# FPGA-Power.net
KiCad netlist of a schematic drawn in Altium Designer
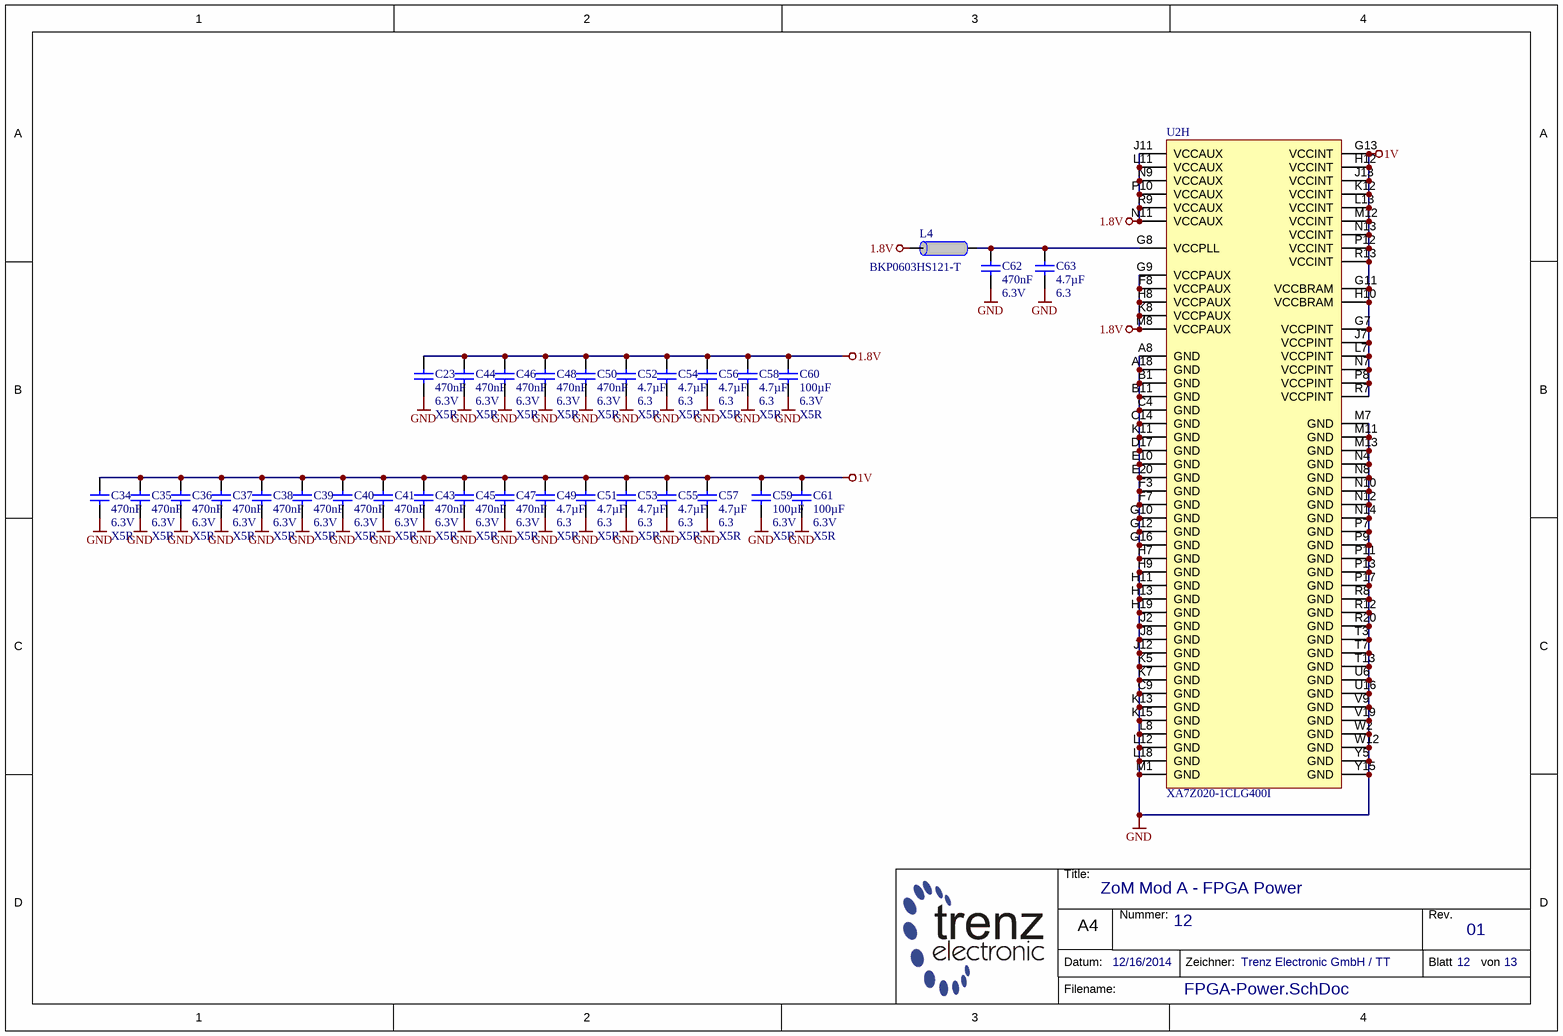
[diagram p0: FPGA-Power.SchDoc]

(export (version "E")
  (design (tool "Eeschema 10.0.6"))
  (components
    (comp (ref "C23")
      (value "470nF")
      (footprint "CAPC0603X33N")
      (description "KON 470nF X5R 6.3V SMD")
      (fields
        (field (name "VOLTAGE") "6.3V")
        (field (name "TECHNOLOGY") "X5R")
        (field (name "TOLERANCE") "20%")
      )
      (libsource (lib "TE") (part "CAP-NP"))
    )
    (comp (ref "C34")
      (value "470nF")
      (footprint "CAPC0603X33N")
      (description "KON 470nF X5R 6.3V SMD")
      (fields
        (field (name "VOLTAGE") "6.3V")
        (field (name "TECHNOLOGY") "X5R")
        (field (name "TOLERANCE") "20%")
      )
      (libsource (lib "TE") (part "CAP-NP"))
    )
    (comp (ref "C35")
      (value "470nF")
      (footprint "CAPC0603X33N")
      (description "KON 470nF X5R 6.3V SMD")
      (fields
        (field (name "VOLTAGE") "6.3V")
        (field (name "TECHNOLOGY") "X5R")
        (field (name "TOLERANCE") "20%")
      )
      (libsource (lib "TE") (part "CAP-NP"))
    )
    (comp (ref "C36")
      (value "470nF")
      (footprint "CAPC0603X33N")
      (description "KON 470nF X5R 6.3V SMD")
      (fields
        (field (name "VOLTAGE") "6.3V")
        (field (name "TECHNOLOGY") "X5R")
        (field (name "TOLERANCE") "20%")
      )
      (libsource (lib "TE") (part "CAP-NP"))
    )
    (comp (ref "C37")
      (value "470nF")
      (footprint "CAPC0603X33N")
      (description "KON 470nF X5R 6.3V SMD")
      (fields
        (field (name "VOLTAGE") "6.3V")
        (field (name "TECHNOLOGY") "X5R")
        (field (name "TOLERANCE") "20%")
      )
      (libsource (lib "TE") (part "CAP-NP"))
    )
    (comp (ref "C38")
      (value "470nF")
      (footprint "CAPC0603X33N")
      (description "KON 470nF X5R 6.3V SMD")
      (fields
        (field (name "VOLTAGE") "6.3V")
        (field (name "TECHNOLOGY") "X5R")
        (field (name "TOLERANCE") "20%")
      )
      (libsource (lib "TE") (part "CAP-NP"))
    )
    (comp (ref "C39")
      (value "470nF")
      (footprint "CAPC0603X33N")
      (description "KON 470nF X5R 6.3V SMD")
      (fields
        (field (name "VOLTAGE") "6.3V")
        (field (name "TECHNOLOGY") "X5R")
        (field (name "TOLERANCE") "20%")
      )
      (libsource (lib "TE") (part "CAP-NP"))
    )
    (comp (ref "C40")
      (value "470nF")
      (footprint "CAPC0603X33N")
      (description "KON 470nF X5R 6.3V SMD")
      (fields
        (field (name "VOLTAGE") "6.3V")
        (field (name "TECHNOLOGY") "X5R")
        (field (name "TOLERANCE") "20%")
      )
      (libsource (lib "TE") (part "CAP-NP"))
    )
    (comp (ref "C41")
      (value "470nF")
      (footprint "CAPC0603X33N")
      (description "KON 470nF X5R 6.3V SMD")
      (fields
        (field (name "VOLTAGE") "6.3V")
        (field (name "TECHNOLOGY") "X5R")
        (field (name "TOLERANCE") "20%")
      )
      (libsource (lib "TE") (part "CAP-NP"))
    )
    (comp (ref "C43")
      (value "470nF")
      (footprint "CAPC0603X33N")
      (description "KON 470nF X5R 6.3V SMD")
      (fields
        (field (name "VOLTAGE") "6.3V")
        (field (name "TECHNOLOGY") "X5R")
        (field (name "TOLERANCE") "20%")
      )
      (libsource (lib "TE") (part "CAP-NP"))
    )
    (comp (ref "C44")
      (value "470nF")
      (footprint "CAPC0603X33N")
      (description "KON 470nF X5R 6.3V SMD")
      (fields
        (field (name "VOLTAGE") "6.3V")
        (field (name "TECHNOLOGY") "X5R")
        (field (name "TOLERANCE") "20%")
      )
      (libsource (lib "TE") (part "CAP-NP"))
    )
    (comp (ref "C45")
      (value "470nF")
      (footprint "CAPC0603X33N")
      (description "KON 470nF X5R 6.3V SMD")
      (fields
        (field (name "VOLTAGE") "6.3V")
        (field (name "TECHNOLOGY") "X5R")
        (field (name "TOLERANCE") "20%")
      )
      (libsource (lib "TE") (part "CAP-NP"))
    )
    (comp (ref "C46")
      (value "470nF")
      (footprint "CAPC0603X33N")
      (description "KON 470nF X5R 6.3V SMD")
      (fields
        (field (name "VOLTAGE") "6.3V")
        (field (name "TECHNOLOGY") "X5R")
        (field (name "TOLERANCE") "20%")
      )
      (libsource (lib "TE") (part "CAP-NP"))
    )
    (comp (ref "C47")
      (value "470nF")
      (footprint "CAPC0603X33N")
      (description "KON 470nF X5R 6.3V SMD")
      (fields
        (field (name "VOLTAGE") "6.3V")
        (field (name "TECHNOLOGY") "X5R")
        (field (name "TOLERANCE") "20%")
      )
      (libsource (lib "TE") (part "CAP-NP"))
    )
    (comp (ref "C48")
      (value "470nF")
      (footprint "CAPC0603X33N")
      (description "KON 470nF X5R 6.3V SMD")
      (fields
        (field (name "VOLTAGE") "6.3V")
        (field (name "TECHNOLOGY") "X5R")
        (field (name "TOLERANCE") "20%")
      )
      (libsource (lib "TE") (part "CAP-NP"))
    )
    (comp (ref "C49")
      (value "4.7µF")
      (footprint "CAPC1005X60N")
      (description "KON 4.7µF 6.3V X5R SMD")
      (fields (field (name "VOLTAGE") "6.3") (field (name "TECHNOLOGY") "X5R"))
      (libsource (lib "TE") (part "CAP-NP"))
    )
    (comp (ref "C50")
      (value "470nF")
      (footprint "CAPC0603X33N")
      (description "KON 470nF X5R 6.3V SMD")
      (fields
        (field (name "VOLTAGE") "6.3V")
        (field (name "TECHNOLOGY") "X5R")
        (field (name "TOLERANCE") "20%")
      )
      (libsource (lib "TE") (part "CAP-NP"))
    )
    (comp (ref "C51")
      (value "4.7µF")
      (footprint "CAPC1005X60N")
      (description "KON 4.7µF 6.3V X5R SMD")
      (fields (field (name "VOLTAGE") "6.3") (field (name "TECHNOLOGY") "X5R"))
      (libsource (lib "TE") (part "CAP-NP"))
    )
    (comp (ref "C52")
      (value "4.7µF")
      (footprint "CAPC1005X60N")
      (description "KON 4.7µF 6.3V X5R SMD")
      (fields (field (name "VOLTAGE") "6.3") (field (name "TECHNOLOGY") "X5R"))
      (libsource (lib "TE") (part "CAP-NP"))
    )
    (comp (ref "C53")
      (value "4.7µF")
      (footprint "CAPC1005X60N")
      (description "KON 4.7µF 6.3V X5R SMD")
      (fields (field (name "VOLTAGE") "6.3") (field (name "TECHNOLOGY") "X5R"))
      (libsource (lib "TE") (part "CAP-NP"))
    )
    (comp (ref "C54")
      (value "4.7µF")
      (footprint "CAPC1005X60N")
      (description "KON 4.7µF 6.3V X5R SMD")
      (fields (field (name "VOLTAGE") "6.3") (field (name "TECHNOLOGY") "X5R"))
      (libsource (lib "TE") (part "CAP-NP"))
    )
    (comp (ref "C55")
      (value "4.7µF")
      (footprint "CAPC1005X60N")
      (description "KON 4.7µF 6.3V X5R SMD")
      (fields (field (name "VOLTAGE") "6.3") (field (name "TECHNOLOGY") "X5R"))
      (libsource (lib "TE") (part "CAP-NP"))
    )
    (comp (ref "C56")
      (value "4.7µF")
      (footprint "CAPC1005X60N")
      (description "KON 4.7µF 6.3V X5R SMD")
      (fields (field (name "VOLTAGE") "6.3") (field (name "TECHNOLOGY") "X5R"))
      (libsource (lib "TE") (part "CAP-NP"))
    )
    (comp (ref "C57")
      (value "4.7µF")
      (footprint "CAPC1005X60N")
      (description "KON 4.7µF 6.3V X5R SMD")
      (fields (field (name "VOLTAGE") "6.3") (field (name "TECHNOLOGY") "X5R"))
      (libsource (lib "TE") (part "CAP-NP"))
    )
    (comp (ref "C58")
      (value "4.7µF")
      (footprint "CAPC1005X60N")
      (description "KON 4.7µF 6.3V X5R SMD")
      (fields (field (name "VOLTAGE") "6.3") (field (name "TECHNOLOGY") "X5R"))
      (libsource (lib "TE") (part "CAP-NP"))
    )
    (comp (ref "C59")
      (value "100µF")
      (footprint "CAPC3216X180N")
      (description "KON 100µF 6,3V X5R SMD")
      (fields (field (name "VOLTAGE") "6.3V") (field (name "TECHNOLOGY") "X5R"))
      (libsource (lib "TE") (part "CAP-NP"))
    )
    (comp (ref "C60")
      (value "100µF")
      (footprint "CAPC3216X180N")
      (description "KON 100µF 6,3V X5R SMD")
      (fields (field (name "VOLTAGE") "6.3V") (field (name "TECHNOLOGY") "X5R"))
      (libsource (lib "TE") (part "CAP-NP"))
    )
    (comp (ref "C61")
      (value "100µF")
      (footprint "CAPC3216X180N")
      (description "KON 100µF 6,3V X5R SMD")
      (fields (field (name "VOLTAGE") "6.3V") (field (name "TECHNOLOGY") "X5R"))
      (libsource (lib "TE") (part "CAP-NP"))
    )
    (comp (ref "C62")
      (value "470nF")
      (footprint "CAPC0603X33N")
      (description "KON 470nF X5R 6.3V SMD")
      (fields (field (name "VOLTAGE") "6.3V") (field (name "TOLERANCE") "20%"))
      (libsource (lib "TE") (part "CAP-NP"))
    )
    (comp (ref "C63")
      (value "4.7µF")
      (footprint "CAPC1005X60N")
      (description "KON 4.7µF 6.3V X5R SMD")
      (fields (field (name "VOLTAGE") "6.3"))
      (libsource (lib "TE") (part "CAP-NP"))
    )
    (comp (ref "L4")
      (value "BKP0603HS121-T")
      (footprint "INDC0603X33N")
      (description "Ferritdurchführung SMD 0201")
      (libsource (lib "TE") (part "Ferritperle"))
    )
    (comp (ref "U2")
      (value "XA7Z020-1CLG400I")
      (footprint "BGA400C80P20X20_1700X1700X160N")
      (libsource (lib "TE") (part "XC7Z020-2CLG400C"))
    )
  )
  (nets
    (net (code "1") (name "1.8V") (class "Default")
      (node (ref "C23") (pin "1") (pinfunction "1_1") (pintype "passive"))
      (node (ref "C44") (pin "1") (pinfunction "1_1") (pintype "passive"))
      (node (ref "C46") (pin "1") (pinfunction "1_1") (pintype "passive"))
      (node (ref "C48") (pin "1") (pinfunction "1_1") (pintype "passive"))
      (node (ref "C50") (pin "1") (pinfunction "1_1") (pintype "passive"))
      (node (ref "C52") (pin "1") (pinfunction "1_1") (pintype "passive"))
      (node (ref "C54") (pin "1") (pinfunction "1_1") (pintype "passive"))
      (node (ref "C56") (pin "1") (pinfunction "1_1") (pintype "passive"))
      (node (ref "C58") (pin "1") (pinfunction "1_1") (pintype "passive"))
      (node (ref "C60") (pin "2") (pinfunction "2_2") (pintype "passive"))
      (node (ref "L4") (pin "2") (pinfunction "2_2") (pintype "passive"))
      (node (ref "U2") (pin "F8") (pinfunction "VCCPAUX_F8") (pintype "power_in"))
      (node (ref "U2") (pin "G9") (pinfunction "VCCPAUX_G9") (pintype "power_in"))
      (node (ref "U2") (pin "H8") (pinfunction "VCCPAUX_H8") (pintype "power_in"))
      (node (ref "U2") (pin "J11") (pinfunction "VCCAUX_J11") (pintype "power_in"))
      (node (ref "U2") (pin "K8") (pinfunction "VCCPAUX_K8") (pintype "power_in"))
      (node (ref "U2") (pin "L11") (pinfunction "VCCAUX_L11") (pintype "power_in"))
      (node (ref "U2") (pin "M8") (pinfunction "VCCPAUX_M8") (pintype "power_in"))
      (node (ref "U2") (pin "N11") (pinfunction "VCCAUX_N11") (pintype "power_in"))
      (node (ref "U2") (pin "N9") (pinfunction "VCCAUX_N9") (pintype "power_in"))
      (node (ref "U2") (pin "P10") (pinfunction "VCCAUX_P10") (pintype "power_in"))
      (node (ref "U2") (pin "R9") (pinfunction "VCCAUX_R9") (pintype "power_in"))
    )
    (net (code "2") (name "1V") (class "Default")
      (node (ref "C34") (pin "1") (pinfunction "1_1") (pintype "passive"))
      (node (ref "C35") (pin "1") (pinfunction "1_1") (pintype "passive"))
      (node (ref "C36") (pin "1") (pinfunction "1_1") (pintype "passive"))
      (node (ref "C37") (pin "1") (pinfunction "1_1") (pintype "passive"))
      (node (ref "C38") (pin "1") (pinfunction "1_1") (pintype "passive"))
      (node (ref "C39") (pin "1") (pinfunction "1_1") (pintype "passive"))
      (node (ref "C40") (pin "1") (pinfunction "1_1") (pintype "passive"))
      (node (ref "C41") (pin "1") (pinfunction "1_1") (pintype "passive"))
      (node (ref "C43") (pin "1") (pinfunction "1_1") (pintype "passive"))
      (node (ref "C45") (pin "1") (pinfunction "1_1") (pintype "passive"))
      (node (ref "C47") (pin "1") (pinfunction "1_1") (pintype "passive"))
      (node (ref "C49") (pin "1") (pinfunction "1_1") (pintype "passive"))
      (node (ref "C51") (pin "1") (pinfunction "1_1") (pintype "passive"))
      (node (ref "C53") (pin "1") (pinfunction "1_1") (pintype "passive"))
      (node (ref "C55") (pin "1") (pinfunction "1_1") (pintype "passive"))
      (node (ref "C57") (pin "1") (pinfunction "1_1") (pintype "passive"))
      (node (ref "C59") (pin "1") (pinfunction "1_1") (pintype "passive"))
      (node (ref "C61") (pin "1") (pinfunction "1_1") (pintype "passive"))
      (node (ref "U2") (pin "G11") (pinfunction "VCCBRAM_G11") (pintype "power_in"))
      (node (ref "U2") (pin "G13") (pinfunction "VCCINT_G13") (pintype "power_in"))
      (node (ref "U2") (pin "G7") (pinfunction "VCCPINT_G7") (pintype "power_in"))
      (node (ref "U2") (pin "H10") (pinfunction "VCCBRAM_H10") (pintype "power_in"))
      (node (ref "U2") (pin "H12") (pinfunction "VCCINT_H12") (pintype "power_in"))
      (node (ref "U2") (pin "J13") (pinfunction "VCCINT_J13") (pintype "power_in"))
      (node (ref "U2") (pin "J7") (pinfunction "VCCPINT_J7") (pintype "power_in"))
      (node (ref "U2") (pin "K12") (pinfunction "VCCINT_K12") (pintype "power_in"))
      (node (ref "U2") (pin "L13") (pinfunction "VCCINT_L13") (pintype "power_in"))
      (node (ref "U2") (pin "L7") (pinfunction "VCCPINT_L7") (pintype "power_in"))
      (node (ref "U2") (pin "M12") (pinfunction "VCCINT_M12") (pintype "power_in"))
      (node (ref "U2") (pin "N13") (pinfunction "VCCINT_N13") (pintype "power_in"))
      (node (ref "U2") (pin "N7") (pinfunction "VCCPINT_N7") (pintype "power_in"))
      (node (ref "U2") (pin "P12") (pinfunction "VCCINT_P12") (pintype "power_in"))
      (node (ref "U2") (pin "P8") (pinfunction "VCCPINT_P8") (pintype "power_in"))
      (node (ref "U2") (pin "R13") (pinfunction "VCCINT_R13") (pintype "power_in"))
      (node (ref "U2") (pin "R7") (pinfunction "VCCPINT_R7") (pintype "power_in"))
    )
    (net (code "3") (name "GND") (class "Default")
      (node (ref "C23") (pin "2") (pinfunction "2_2") (pintype "passive"))
      (node (ref "C34") (pin "2") (pinfunction "2_2") (pintype "passive"))
      (node (ref "C35") (pin "2") (pinfunction "2_2") (pintype "passive"))
      (node (ref "C36") (pin "2") (pinfunction "2_2") (pintype "passive"))
      (node (ref "C37") (pin "2") (pinfunction "2_2") (pintype "passive"))
      (node (ref "C38") (pin "2") (pinfunction "2_2") (pintype "passive"))
      (node (ref "C39") (pin "2") (pinfunction "2_2") (pintype "passive"))
      (node (ref "C40") (pin "2") (pinfunction "2_2") (pintype "passive"))
      (node (ref "C41") (pin "2") (pinfunction "2_2") (pintype "passive"))
      (node (ref "C43") (pin "2") (pinfunction "2_2") (pintype "passive"))
      (node (ref "C44") (pin "2") (pinfunction "2_2") (pintype "passive"))
      (node (ref "C45") (pin "2") (pinfunction "2_2") (pintype "passive"))
      (node (ref "C46") (pin "2") (pinfunction "2_2") (pintype "passive"))
      (node (ref "C47") (pin "2") (pinfunction "2_2") (pintype "passive"))
      (node (ref "C48") (pin "2") (pinfunction "2_2") (pintype "passive"))
      (node (ref "C49") (pin "2") (pinfunction "2_2") (pintype "passive"))
      (node (ref "C50") (pin "2") (pinfunction "2_2") (pintype "passive"))
      (node (ref "C51") (pin "2") (pinfunction "2_2") (pintype "passive"))
      (node (ref "C52") (pin "2") (pinfunction "2_2") (pintype "passive"))
      (node (ref "C53") (pin "2") (pinfunction "2_2") (pintype "passive"))
      (node (ref "C54") (pin "2") (pinfunction "2_2") (pintype "passive"))
      (node (ref "C55") (pin "2") (pinfunction "2_2") (pintype "passive"))
      (node (ref "C56") (pin "2") (pinfunction "2_2") (pintype "passive"))
      (node (ref "C57") (pin "2") (pinfunction "2_2") (pintype "passive"))
      (node (ref "C58") (pin "2") (pinfunction "2_2") (pintype "passive"))
      (node (ref "C59") (pin "2") (pinfunction "2_2") (pintype "passive"))
      (node (ref "C60") (pin "1") (pinfunction "1_1") (pintype "passive"))
      (node (ref "C61") (pin "2") (pinfunction "2_2") (pintype "passive"))
      (node (ref "C62") (pin "2") (pinfunction "2_2") (pintype "passive"))
      (node (ref "C63") (pin "2") (pinfunction "2_2") (pintype "passive"))
      (node (ref "U2") (pin "A18") (pinfunction "GND_A18") (pintype "power_in"))
      (node (ref "U2") (pin "A8") (pinfunction "GND_A8") (pintype "power_in"))
      (node (ref "U2") (pin "B1") (pinfunction "GND_B1") (pintype "power_in"))
      (node (ref "U2") (pin "B11") (pinfunction "GND_B11") (pintype "power_in"))
      (node (ref "U2") (pin "C14") (pinfunction "GND_C14") (pintype "power_in"))
      (node (ref "U2") (pin "C4") (pinfunction "GND_C4") (pintype "power_in"))
      (node (ref "U2") (pin "C9") (pinfunction "GND_C9") (pintype "power_in"))
      (node (ref "U2") (pin "D17") (pinfunction "GND_D17") (pintype "power_in"))
      (node (ref "U2") (pin "E10") (pinfunction "GND_E10") (pintype "power_in"))
      (node (ref "U2") (pin "E20") (pinfunction "GND_E20") (pintype "power_in"))
      (node (ref "U2") (pin "F3") (pinfunction "GND_F3") (pintype "power_in"))
      (node (ref "U2") (pin "F7") (pinfunction "GND_F7") (pintype "power_in"))
      (node (ref "U2") (pin "G10") (pinfunction "GND_G10") (pintype "power_in"))
      (node (ref "U2") (pin "G12") (pinfunction "GND_G12") (pintype "power_in"))
      (node (ref "U2") (pin "G16") (pinfunction "GND_G16") (pintype "power_in"))
      (node (ref "U2") (pin "H11") (pinfunction "GND_H11") (pintype "power_in"))
      (node (ref "U2") (pin "H13") (pinfunction "GND_H13") (pintype "power_in"))
      (node (ref "U2") (pin "H19") (pinfunction "GND_H19") (pintype "power_in"))
      (node (ref "U2") (pin "H7") (pinfunction "GND_H7") (pintype "power_in"))
      (node (ref "U2") (pin "H9") (pinfunction "GND_H9") (pintype "power_in"))
      (node (ref "U2") (pin "J12") (pinfunction "GND_J12") (pintype "power_in"))
      (node (ref "U2") (pin "J2") (pinfunction "GND_J2") (pintype "power_in"))
      (node (ref "U2") (pin "J8") (pinfunction "GND_J8") (pintype "power_in"))
      (node (ref "U2") (pin "K11") (pinfunction "GND_K11") (pintype "power_in"))
      (node (ref "U2") (pin "K13") (pinfunction "GND_K13") (pintype "power_in"))
      (node (ref "U2") (pin "K15") (pinfunction "GND_K15") (pintype "power_in"))
      (node (ref "U2") (pin "K5") (pinfunction "GND_K5") (pintype "power_in"))
      (node (ref "U2") (pin "K7") (pinfunction "GND_K7") (pintype "power_in"))
      (node (ref "U2") (pin "L12") (pinfunction "GND_L12") (pintype "power_in"))
      (node (ref "U2") (pin "L18") (pinfunction "GND_L18") (pintype "power_in"))
      (node (ref "U2") (pin "L8") (pinfunction "GND_L8") (pintype "power_in"))
      (node (ref "U2") (pin "M1") (pinfunction "GND_M1") (pintype "power_in"))
      (node (ref "U2") (pin "M11") (pinfunction "GND_M11") (pintype "power_in"))
      (node (ref "U2") (pin "M13") (pinfunction "GND_M13") (pintype "power_in"))
      (node (ref "U2") (pin "M7") (pinfunction "GND_M7") (pintype "power_in"))
      (node (ref "U2") (pin "N10") (pinfunction "GND_N10") (pintype "power_in"))
      (node (ref "U2") (pin "N12") (pinfunction "GND_N12") (pintype "power_in"))
      (node (ref "U2") (pin "N14") (pinfunction "GND_N14") (pintype "power_in"))
      (node (ref "U2") (pin "N4") (pinfunction "GND_N4") (pintype "power_in"))
      (node (ref "U2") (pin "N8") (pinfunction "GND_N8") (pintype "power_in"))
      (node (ref "U2") (pin "P11") (pinfunction "GND_P11") (pintype "power_in"))
      (node (ref "U2") (pin "P13") (pinfunction "GND_P13") (pintype "power_in"))
      (node (ref "U2") (pin "P17") (pinfunction "GND_P17") (pintype "power_in"))
      (node (ref "U2") (pin "P7") (pinfunction "GND_P7") (pintype "power_in"))
      (node (ref "U2") (pin "P9") (pinfunction "GND_P9") (pintype "power_in"))
      (node (ref "U2") (pin "R12") (pinfunction "GND_R12") (pintype "power_in"))
      (node (ref "U2") (pin "R20") (pinfunction "GND_R20") (pintype "power_in"))
      (node (ref "U2") (pin "R8") (pinfunction "GND_R8") (pintype "power_in"))
      (node (ref "U2") (pin "T13") (pinfunction "GND_T13") (pintype "power_in"))
      (node (ref "U2") (pin "T3") (pinfunction "GND_T3") (pintype "power_in"))
      (node (ref "U2") (pin "T7") (pinfunction "GND_T7") (pintype "power_in"))
      (node (ref "U2") (pin "U16") (pinfunction "GND_U16") (pintype "power_in"))
      (node (ref "U2") (pin "U6") (pinfunction "GND_U6") (pintype "power_in"))
      (node (ref "U2") (pin "V19") (pinfunction "GND_V19") (pintype "power_in"))
      (node (ref "U2") (pin "V9") (pinfunction "GND_V9") (pintype "power_in"))
      (node (ref "U2") (pin "W12") (pinfunction "GND_W12") (pintype "power_in"))
      (node (ref "U2") (pin "W2") (pinfunction "GND_W2") (pintype "power_in"))
      (node (ref "U2") (pin "Y15") (pinfunction "GND_Y15") (pintype "power_in"))
      (node (ref "U2") (pin "Y5") (pinfunction "GND_Y5") (pintype "power_in"))
    )
    (net (code "4") (name "Net-(U2H-VCCPLL)") (class "Default")
      (node (ref "C62") (pin "1") (pinfunction "1_1") (pintype "passive"))
      (node (ref "C63") (pin "1") (pinfunction "1_1") (pintype "passive"))
      (node (ref "L4") (pin "1") (pinfunction "1_1") (pintype "passive"))
      (node (ref "U2") (pin "G8") (pinfunction "VCCPLL_G8") (pintype "power_in"))
    )
  )
)
